# DC-DC_Regulator.net
KiCad netlist of a schematic drawn in Altium Designer
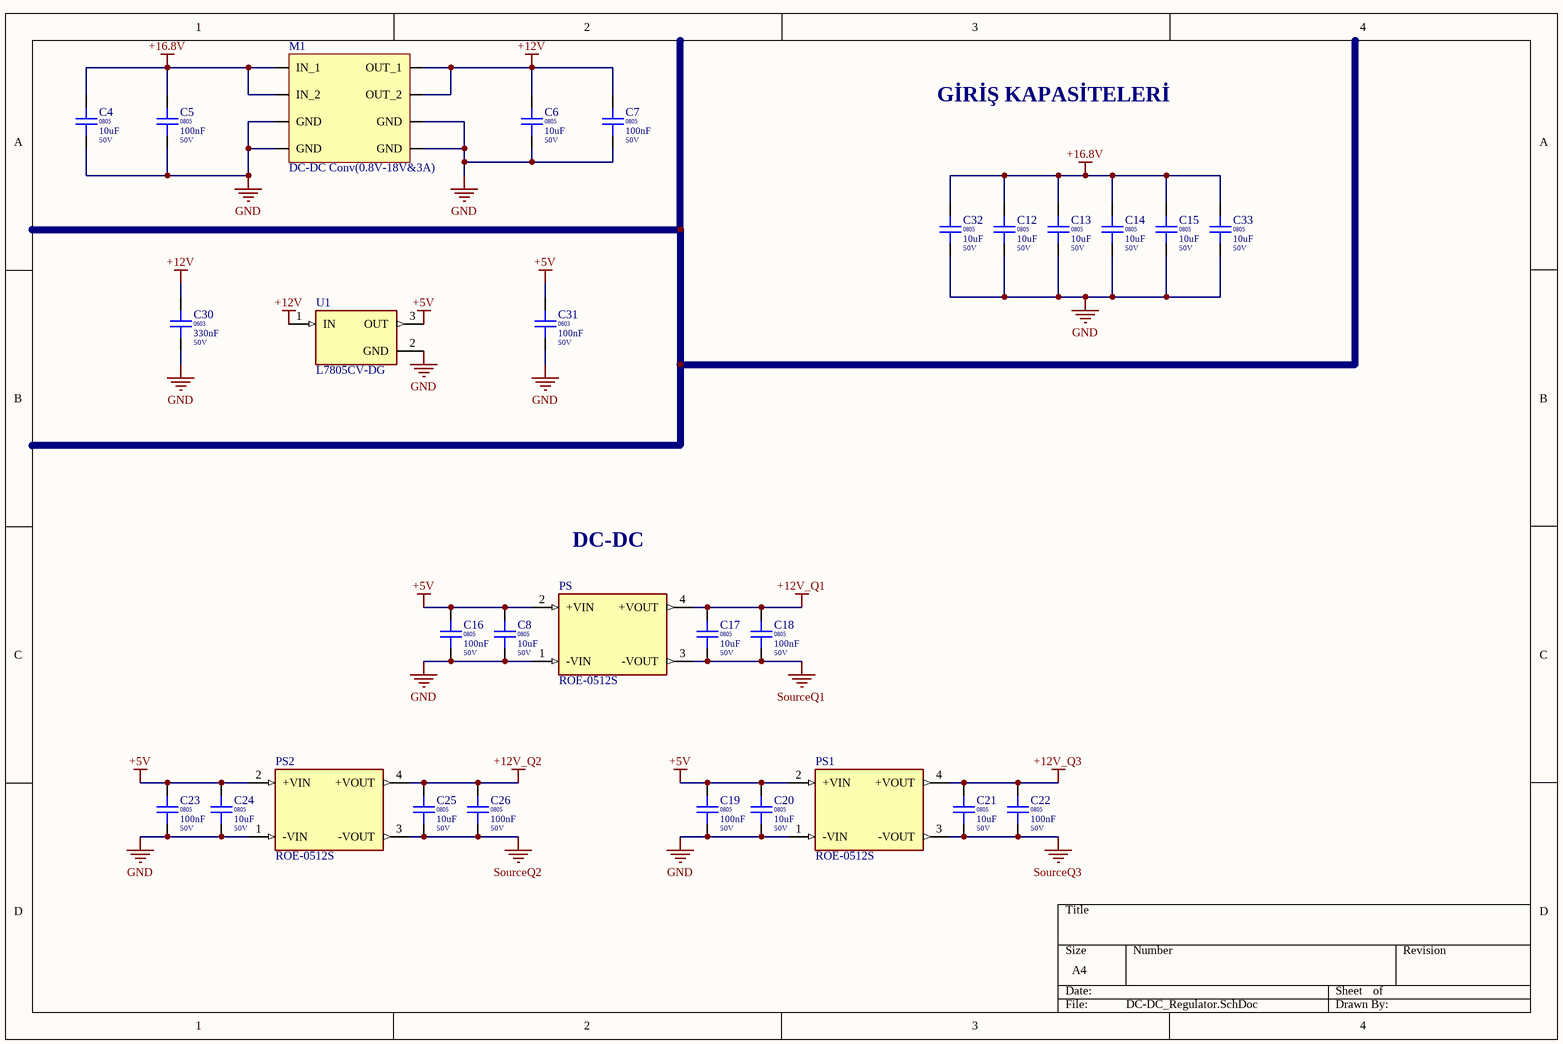
[diagram p0: DC-DC_Regulator.SchDoc]

(export (version "E")
  (design (tool "Eeschema 10.0.6"))
  (components
    (comp (ref "C4")
      (value "10uF")
      (footprint "CAPC 0805")
      (description "Capacitor Ceramic 10uF 50V 0805")
      (fields
        (field (name "PACKAGE / CASE") "0805")
        (field (name "VOLTAGE") "50V")
        (field (name "PART NUMBER") "CAPC0588")
      )
      (libsource (lib "Aesk Database Library") (part "NPCapacitor"))
    )
    (comp (ref "C5")
      (value "100nF")
      (footprint "CAPC 0805")
      (description "Capacitor Ceramic 100nF 50V 0805")
      (fields
        (field (name "PACKAGE / CASE") "0805")
        (field (name "VOLTAGE") "50V")
        (field (name "PART NUMBER") "CAPC0572")
      )
      (libsource (lib "Aesk Database Library") (part "NPCapacitor"))
    )
    (comp (ref "C6")
      (value "10uF")
      (footprint "CAPC 0805")
      (description "Capacitor Ceramic 10uF 50V 0805")
      (fields
        (field (name "PACKAGE / CASE") "0805")
        (field (name "VOLTAGE") "50V")
        (field (name "PART NUMBER") "CAPC0588")
      )
      (libsource (lib "Aesk Database Library") (part "NPCapacitor"))
    )
    (comp (ref "C7")
      (value "100nF")
      (footprint "CAPC 0805")
      (description "Capacitor Ceramic 100nF 50V 0805")
      (fields
        (field (name "PACKAGE / CASE") "0805")
        (field (name "VOLTAGE") "50V")
        (field (name "PART NUMBER") "CAPC0572")
      )
      (libsource (lib "Aesk Database Library") (part "NPCapacitor"))
    )
    (comp (ref "C8")
      (value "10uF")
      (footprint "CAPC 0805")
      (description "Capacitor Ceramic 10uF 50V 0805")
      (fields
        (field (name "TOLERANCE") "%10")
        (field (name "PACKAGE / CASE") "0805")
        (field (name "VOLTAGE") "50V")
        (field (name "PART NUMBER") "CAPC0588")
      )
      (libsource (lib "AESK Database Library") (part "NPCapacitor"))
    )
    (comp (ref "C12")
      (value "10uF")
      (footprint "CAPC 0805")
      (description "Capacitor Ceramic 10uF 50V 0805")
      (fields
        (field (name "PACKAGE / CASE") "0805")
        (field (name "VOLTAGE") "50V")
        (field (name "PART NUMBER") "CAPC0588")
      )
      (libsource (lib "Aesk Database Library") (part "NPCapacitor"))
    )
    (comp (ref "C13")
      (value "10uF")
      (footprint "CAPC 0805")
      (description "Capacitor Ceramic 10uF 50V 0805")
      (fields
        (field (name "PACKAGE / CASE") "0805")
        (field (name "VOLTAGE") "50V")
        (field (name "PART NUMBER") "CAPC0588")
      )
      (libsource (lib "Aesk Database Library") (part "NPCapacitor"))
    )
    (comp (ref "C14")
      (value "10uF")
      (footprint "CAPC 0805")
      (description "Capacitor Ceramic 10uF 50V 0805")
      (fields
        (field (name "PACKAGE / CASE") "0805")
        (field (name "VOLTAGE") "50V")
        (field (name "PART NUMBER") "CAPC0588")
      )
      (libsource (lib "Aesk Database Library") (part "NPCapacitor"))
    )
    (comp (ref "C15")
      (value "10uF")
      (footprint "CAPC 0805")
      (description "Capacitor Ceramic 10uF 50V 0805")
      (fields
        (field (name "PACKAGE / CASE") "0805")
        (field (name "VOLTAGE") "50V")
        (field (name "PART NUMBER") "CAPC0588")
      )
      (libsource (lib "Aesk Database Library") (part "NPCapacitor"))
    )
    (comp (ref "C16")
      (value "100nF")
      (footprint "CAPC 0805")
      (description "Capacitor Ceramic 100nF 50V 0805")
      (fields
        (field (name "PACKAGE / CASE") "0805")
        (field (name "VOLTAGE") "50V")
        (field (name "PART NUMBER") "CAPC0572")
      )
      (libsource (lib "Aesk Database Library") (part "NPCapacitor"))
    )
    (comp (ref "C17")
      (value "10uF")
      (footprint "CAPC 0805")
      (description "Capacitor Ceramic 10uF 50V 0805")
      (fields
        (field (name "TOLERANCE") "%10")
        (field (name "PACKAGE / CASE") "0805")
        (field (name "VOLTAGE") "50V")
        (field (name "PART NUMBER") "CAPC0588")
      )
      (libsource (lib "AESK Database Library") (part "NPCapacitor"))
    )
    (comp (ref "C18")
      (value "100nF")
      (footprint "CAPC 0805")
      (description "Capacitor Ceramic 100nF 50V 0805")
      (fields
        (field (name "PACKAGE / CASE") "0805")
        (field (name "VOLTAGE") "50V")
        (field (name "PART NUMBER") "CAPC0572")
      )
      (libsource (lib "Aesk Database Library") (part "NPCapacitor"))
    )
    (comp (ref "C19")
      (value "100nF")
      (footprint "CAPC 0805")
      (description "Capacitor Ceramic 100nF 50V 0805")
      (fields
        (field (name "PACKAGE / CASE") "0805")
        (field (name "VOLTAGE") "50V")
        (field (name "PART NUMBER") "CAPC0572")
      )
      (libsource (lib "Aesk Database Library") (part "NPCapacitor"))
    )
    (comp (ref "C20")
      (value "10uF")
      (footprint "CAPC 0805")
      (description "Capacitor Ceramic 10uF 50V 0805")
      (fields
        (field (name "TOLERANCE") "%10")
        (field (name "PACKAGE / CASE") "0805")
        (field (name "VOLTAGE") "50V")
        (field (name "PART NUMBER") "CAPC0588")
      )
      (libsource (lib "AESK Database Library") (part "NPCapacitor"))
    )
    (comp (ref "C21")
      (value "10uF")
      (footprint "CAPC 0805")
      (description "Capacitor Ceramic 10uF 50V 0805")
      (fields
        (field (name "TOLERANCE") "%10")
        (field (name "PACKAGE / CASE") "0805")
        (field (name "VOLTAGE") "50V")
        (field (name "PART NUMBER") "CAPC0588")
      )
      (libsource (lib "AESK Database Library") (part "NPCapacitor"))
    )
    (comp (ref "C22")
      (value "100nF")
      (footprint "CAPC 0805")
      (description "Capacitor Ceramic 100nF 50V 0805")
      (fields
        (field (name "PACKAGE / CASE") "0805")
        (field (name "VOLTAGE") "50V")
        (field (name "PART NUMBER") "CAPC0572")
      )
      (libsource (lib "Aesk Database Library") (part "NPCapacitor"))
    )
    (comp (ref "C23")
      (value "100nF")
      (footprint "CAPC 0805")
      (description "Capacitor Ceramic 100nF 50V 0805")
      (fields
        (field (name "PACKAGE / CASE") "0805")
        (field (name "VOLTAGE") "50V")
        (field (name "PART NUMBER") "CAPC0572")
      )
      (libsource (lib "Aesk Database Library") (part "NPCapacitor"))
    )
    (comp (ref "C24")
      (value "10uF")
      (footprint "CAPC 0805")
      (description "Capacitor Ceramic 10uF 50V 0805")
      (fields
        (field (name "TOLERANCE") "%10")
        (field (name "PACKAGE / CASE") "0805")
        (field (name "VOLTAGE") "50V")
        (field (name "PART NUMBER") "CAPC0588")
      )
      (libsource (lib "AESK Database Library") (part "NPCapacitor"))
    )
    (comp (ref "C25")
      (value "10uF")
      (footprint "CAPC 0805")
      (description "Capacitor Ceramic 10uF 50V 0805")
      (fields
        (field (name "TOLERANCE") "%10")
        (field (name "PACKAGE / CASE") "0805")
        (field (name "VOLTAGE") "50V")
        (field (name "PART NUMBER") "CAPC0588")
      )
      (libsource (lib "AESK Database Library") (part "NPCapacitor"))
    )
    (comp (ref "C26")
      (value "100nF")
      (footprint "CAPC 0805")
      (description "Capacitor Ceramic 100nF 50V 0805")
      (fields
        (field (name "PACKAGE / CASE") "0805")
        (field (name "VOLTAGE") "50V")
        (field (name "PART NUMBER") "CAPC0572")
      )
      (libsource (lib "Aesk Database Library") (part "NPCapacitor"))
    )
    (comp (ref "C30")
      (value "330nF")
      (footprint "CAPC 0603")
      (description "Capacitor Ceramic 330nF 50V 0603")
      (fields
        (field (name "TOLERANCE") "%10")
        (field (name "PACKAGE / CASE") "0603")
        (field (name "VOLTAGE") "50V")
        (field (name "PART NUMBER") "CAPC0288")
      )
      (libsource (lib "AESK Database Library") (part "NPCapacitor"))
    )
    (comp (ref "C31")
      (value "100nF")
      (footprint "CAPC 0603")
      (description "Capacitor Ceramic 100nF 50V 0603")
      (fields
        (field (name "TOLERANCE") "%10")
        (field (name "PACKAGE / CASE") "0603")
        (field (name "VOLTAGE") "50V")
        (field (name "PART NUMBER") "CAPC0285")
      )
      (libsource (lib "AESK Database Library") (part "NPCapacitor"))
    )
    (comp (ref "C32")
      (value "10uF")
      (footprint "CAPC 0805")
      (description "Capacitor Ceramic 10uF 50V 0805")
      (fields
        (field (name "PACKAGE / CASE") "0805")
        (field (name "VOLTAGE") "50V")
        (field (name "PART NUMBER") "CAPC0588")
      )
      (libsource (lib "Aesk Database Library") (part "NPCapacitor"))
    )
    (comp (ref "C33")
      (value "10uF")
      (footprint "CAPC 0805")
      (description "Capacitor Ceramic 10uF 50V 0805")
      (fields
        (field (name "PACKAGE / CASE") "0805")
        (field (name "VOLTAGE") "50V")
        (field (name "PART NUMBER") "CAPC0588")
      )
      (libsource (lib "Aesk Database Library") (part "NPCapacitor"))
    )
    (comp (ref "M1")
      (value "DC-DC Conv(0.8V-18V&3A)")
      (footprint "mp")
      (libsource (lib "UAV_UcusKontrolKartı_Sematik_Kutuphane") (part "MP1584EN"))
    )
    (comp (ref "PS")
      (value "ROE-0512S")
      (footprint "CONV_ROE-0512S")
      (description "1W DC/DC-Converter 'ECONOLINE' SIP4 1kV unreg")
      (fields (field (name "MF") "Recom Power"))
      (libsource (lib "ESC") (part "ROE-0512S"))
    )
    (comp (ref "PS1")
      (value "ROE-0512S")
      (footprint "CONV_ROE-0512S")
      (description "1W DC/DC-Converter 'ECONOLINE' SIP4 1kV unreg")
      (fields (field (name "MF") "Recom Power"))
      (libsource (lib "ESC") (part "ROE-0512S"))
    )
    (comp (ref "PS2")
      (value "ROE-0512S")
      (footprint "CONV_ROE-0512S")
      (description "1W DC/DC-Converter 'ECONOLINE' SIP4 1kV unreg")
      (fields (field (name "MF") "Recom Power"))
      (libsource (lib "ESC") (part "ROE-0512S"))
    )
    (comp (ref "U1")
      (value "L7805CV-DG")
      (footprint "TO255P1040X460X2890-3")
      (description "Linear Voltage Regulator IC Positive Fixed 1 Output 1.5A TO-220")
      (fields (field (name "MF") "STMicroelectronics"))
      (libsource (lib "ESC") (part "L7805CV-DG"))
    )
  )
  (nets
    (net (code "1") (name "+5V") (class "Default")
      (node (ref "C16") (pin "2") (pinfunction "2_2") (pintype "passive"))
      (node (ref "C19") (pin "2") (pinfunction "2_2") (pintype "passive"))
      (node (ref "C20") (pin "2") (pinfunction "2_2") (pintype "passive"))
      (node (ref "C23") (pin "2") (pinfunction "2_2") (pintype "passive"))
      (node (ref "C24") (pin "2") (pinfunction "2_2") (pintype "passive"))
      (node (ref "C31") (pin "2") (pinfunction "2_2") (pintype "passive"))
      (node (ref "C8") (pin "2") (pinfunction "2_2") (pintype "passive"))
      (node (ref "PS") (pin "2") (pinfunction "+VIN_2") (pintype "input"))
      (node (ref "PS1") (pin "2") (pinfunction "+VIN_2") (pintype "input"))
      (node (ref "PS2") (pin "2") (pinfunction "+VIN_2") (pintype "input"))
      (node (ref "U1") (pin "3") (pinfunction "OUT_3") (pintype "output"))
    )
    (net (code "2") (name "+12V") (class "Default")
      (node (ref "C30") (pin "2") (pinfunction "2_2") (pintype "passive"))
      (node (ref "C6") (pin "2") (pinfunction "2_2") (pintype "passive"))
      (node (ref "C7") (pin "2") (pinfunction "2_2") (pintype "passive"))
      (node (ref "M1") (pin "3") (pinfunction "OUT_1_3") (pintype "passive"))
      (node (ref "M1") (pin "4") (pinfunction "OUT_2_4") (pintype "passive"))
      (node (ref "U1") (pin "1") (pinfunction "IN_1") (pintype "input"))
    )
    (net (code "3") (name "+12V_Q1") (class "Default")
      (node (ref "C17") (pin "2") (pinfunction "2_2") (pintype "passive"))
      (node (ref "C18") (pin "2") (pinfunction "2_2") (pintype "passive"))
      (node (ref "PS") (pin "4") (pinfunction "+VOUT_4") (pintype "output"))
    )
    (net (code "4") (name "+12V_Q2") (class "Default")
      (node (ref "C25") (pin "2") (pinfunction "2_2") (pintype "passive"))
      (node (ref "C26") (pin "2") (pinfunction "2_2") (pintype "passive"))
      (node (ref "PS2") (pin "4") (pinfunction "+VOUT_4") (pintype "output"))
    )
    (net (code "5") (name "+12V_Q3") (class "Default")
      (node (ref "C21") (pin "2") (pinfunction "2_2") (pintype "passive"))
      (node (ref "C22") (pin "2") (pinfunction "2_2") (pintype "passive"))
      (node (ref "PS1") (pin "4") (pinfunction "+VOUT_4") (pintype "output"))
    )
    (net (code "6") (name "+16.8V") (class "Default")
      (node (ref "C12") (pin "2") (pinfunction "2_2") (pintype "passive"))
      (node (ref "C13") (pin "2") (pinfunction "2_2") (pintype "passive"))
      (node (ref "C14") (pin "2") (pinfunction "2_2") (pintype "passive"))
      (node (ref "C15") (pin "2") (pinfunction "2_2") (pintype "passive"))
      (node (ref "C32") (pin "2") (pinfunction "2_2") (pintype "passive"))
      (node (ref "C33") (pin "2") (pinfunction "2_2") (pintype "passive"))
      (node (ref "C4") (pin "2") (pinfunction "2_2") (pintype "passive"))
      (node (ref "C5") (pin "2") (pinfunction "2_2") (pintype "passive"))
      (node (ref "M1") (pin "1") (pinfunction "IN_1_1") (pintype "passive"))
      (node (ref "M1") (pin "2") (pinfunction "IN_2_2") (pintype "passive"))
    )
    (net (code "7") (name "GND") (class "Default")
      (node (ref "C12") (pin "1") (pinfunction "1_1") (pintype "passive"))
      (node (ref "C13") (pin "1") (pinfunction "1_1") (pintype "passive"))
      (node (ref "C14") (pin "1") (pinfunction "1_1") (pintype "passive"))
      (node (ref "C15") (pin "1") (pinfunction "1_1") (pintype "passive"))
      (node (ref "C16") (pin "1") (pinfunction "1_1") (pintype "passive"))
      (node (ref "C19") (pin "1") (pinfunction "1_1") (pintype "passive"))
      (node (ref "C20") (pin "1") (pinfunction "1_1") (pintype "passive"))
      (node (ref "C23") (pin "1") (pinfunction "1_1") (pintype "passive"))
      (node (ref "C24") (pin "1") (pinfunction "1_1") (pintype "passive"))
      (node (ref "C30") (pin "1") (pinfunction "1_1") (pintype "passive"))
      (node (ref "C31") (pin "1") (pinfunction "1_1") (pintype "passive"))
      (node (ref "C32") (pin "1") (pinfunction "1_1") (pintype "passive"))
      (node (ref "C33") (pin "1") (pinfunction "1_1") (pintype "passive"))
      (node (ref "C4") (pin "1") (pinfunction "1_1") (pintype "passive"))
      (node (ref "C5") (pin "1") (pinfunction "1_1") (pintype "passive"))
      (node (ref "C6") (pin "1") (pinfunction "1_1") (pintype "passive"))
      (node (ref "C7") (pin "1") (pinfunction "1_1") (pintype "passive"))
      (node (ref "C8") (pin "1") (pinfunction "1_1") (pintype "passive"))
      (node (ref "M1") (pin "5") (pinfunction "GND_5") (pintype "passive"))
      (node (ref "M1") (pin "6") (pinfunction "GND_6") (pintype "passive"))
      (node (ref "M1") (pin "7") (pinfunction "GND_7") (pintype "passive"))
      (node (ref "M1") (pin "8") (pinfunction "GND_8") (pintype "passive"))
      (node (ref "PS") (pin "1") (pinfunction "-VIN_1") (pintype "input"))
      (node (ref "PS1") (pin "1") (pinfunction "-VIN_1") (pintype "input"))
      (node (ref "PS2") (pin "1") (pinfunction "-VIN_1") (pintype "input"))
      (node (ref "U1") (pin "2") (pinfunction "GND_2") (pintype "power_in"))
    )
    (net (code "8") (name "SourceQ1") (class "Default")
      (node (ref "C17") (pin "1") (pinfunction "1_1") (pintype "passive"))
      (node (ref "C18") (pin "1") (pinfunction "1_1") (pintype "passive"))
      (node (ref "PS") (pin "3") (pinfunction "-VOUT_3") (pintype "output"))
    )
    (net (code "9") (name "SourceQ2") (class "Default")
      (node (ref "C25") (pin "1") (pinfunction "1_1") (pintype "passive"))
      (node (ref "C26") (pin "1") (pinfunction "1_1") (pintype "passive"))
      (node (ref "PS2") (pin "3") (pinfunction "-VOUT_3") (pintype "output"))
    )
    (net (code "10") (name "SourceQ3") (class "Default")
      (node (ref "C21") (pin "1") (pinfunction "1_1") (pintype "passive"))
      (node (ref "C22") (pin "1") (pinfunction "1_1") (pintype "passive"))
      (node (ref "PS1") (pin "3") (pinfunction "-VOUT_3") (pintype "output"))
    )
  )
)
